# EXP_Headers.net
KiCad netlist of a schematic drawn in Altium Designer
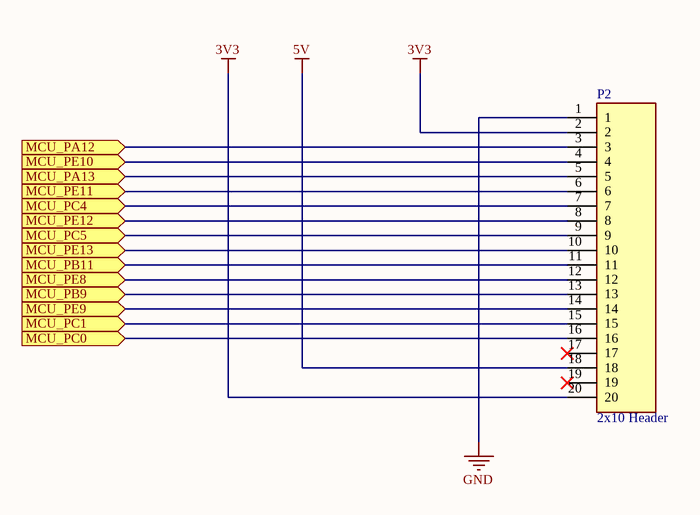
[diagram p0: EXP_Headers.SchDoc]

(export (version "E")
  (design (tool "Eeschema 10.0.6"))
  (components
    (comp (ref "P2")
      (value "2x10 Header")
      (footprint "2x10 Header")
      (description "HE2P-20G6C394-5R, 2.54 mm pegs.")
      (fields (field (name "MP") "1-826944-0") (field (name "MF") "TE Connectivity"))
      (libsource (lib "nnts") (part "2x10 Header"))
    )
  )
  (nets
    (net (code "1") (name "/MCU_PA12") (class "Default")
      (node (ref "P2") (pin "3") (pinfunction "3_3") (pintype "passive"))
    )
    (net (code "2") (name "/MCU_PA13") (class "Default")
      (node (ref "P2") (pin "5") (pinfunction "5_5") (pintype "passive"))
    )
    (net (code "3") (name "/MCU_PB9") (class "Default")
      (node (ref "P2") (pin "13") (pinfunction "13_13") (pintype "passive"))
    )
    (net (code "4") (name "/MCU_PB11") (class "Default")
      (node (ref "P2") (pin "11") (pinfunction "11_11") (pintype "passive"))
    )
    (net (code "5") (name "/MCU_PC0") (class "Default")
      (node (ref "P2") (pin "16") (pinfunction "16_16") (pintype "passive"))
    )
    (net (code "6") (name "/MCU_PC1") (class "Default")
      (node (ref "P2") (pin "15") (pinfunction "15_15") (pintype "passive"))
    )
    (net (code "7") (name "/MCU_PC4") (class "Default")
      (node (ref "P2") (pin "7") (pinfunction "7_7") (pintype "passive"))
    )
    (net (code "8") (name "/MCU_PC5") (class "Default")
      (node (ref "P2") (pin "9") (pinfunction "9_9") (pintype "passive"))
    )
    (net (code "9") (name "/MCU_PE8") (class "Default")
      (node (ref "P2") (pin "12") (pinfunction "12_12") (pintype "passive"))
    )
    (net (code "10") (name "/MCU_PE9") (class "Default")
      (node (ref "P2") (pin "14") (pinfunction "14_14") (pintype "passive"))
    )
    (net (code "11") (name "/MCU_PE10") (class "Default")
      (node (ref "P2") (pin "4") (pinfunction "4_4") (pintype "passive"))
    )
    (net (code "12") (name "/MCU_PE11") (class "Default")
      (node (ref "P2") (pin "6") (pinfunction "6_6") (pintype "passive"))
    )
    (net (code "13") (name "/MCU_PE12") (class "Default")
      (node (ref "P2") (pin "8") (pinfunction "8_8") (pintype "passive"))
    )
    (net (code "14") (name "/MCU_PE13") (class "Default")
      (node (ref "P2") (pin "10") (pinfunction "10_10") (pintype "passive"))
    )
    (net (code "15") (name "3V3") (class "Default")
      (node (ref "P2") (pin "2") (pinfunction "2_2") (pintype "passive"))
      (node (ref "P2") (pin "20") (pinfunction "20_20") (pintype "passive"))
    )
    (net (code "16") (name "5V") (class "Default")
      (node (ref "P2") (pin "18") (pinfunction "18_18") (pintype "passive"))
    )
    (net (code "17") (name "GND") (class "Default")
      (node (ref "P2") (pin "1") (pinfunction "1_1") (pintype "passive"))
    )
    (net (code "18") (name "unconnected-(P2-Pad17)") (class "Default")
      (node (ref "P2") (pin "17") (pinfunction "17_17") (pintype "passive+no_connect"))
    )
    (net (code "19") (name "unconnected-(P2-Pad19)") (class "Default")
      (node (ref "P2") (pin "19") (pinfunction "19_19") (pintype "passive+no_connect"))
    )
  )
)
